# heart.net
KiCad netlist of a schematic drawn in EAGLE
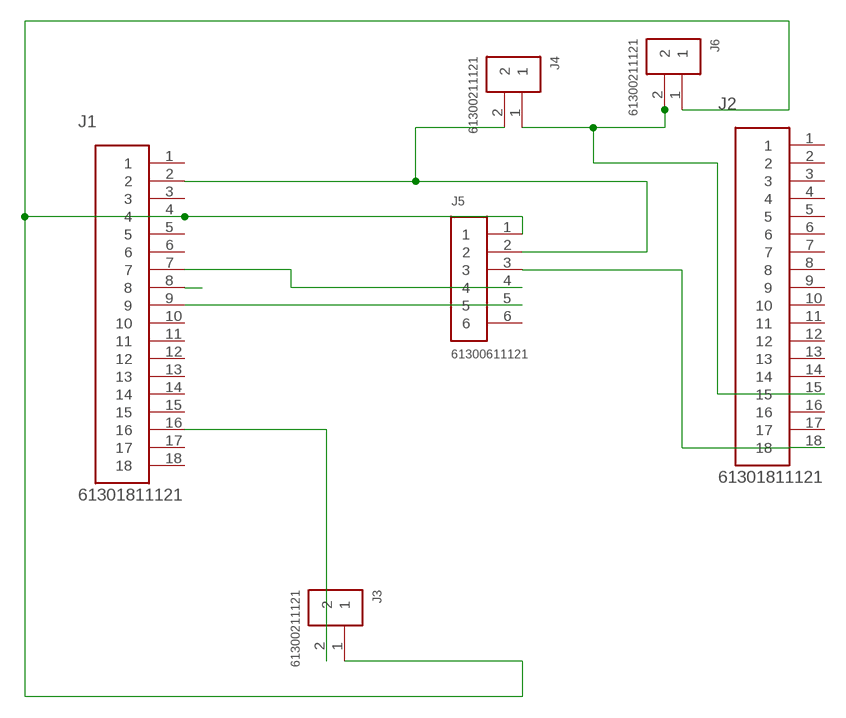
[diagram p0: schematic, sheet 1]

(export (version "E")
  (design (tool "Eeschema 10.0.6"))
  (components
    (comp (ref "J1")
      (value "61301811121")
      (footprint "eagle-import:61301811121")
      (fields
        (field (name "DIGIKEY_PART_NUMBER") "732-5328-ND")
        (field (name "MANUFACTURER") "Wurth Electronics Inc.")
        (field (name "CREATED_BY") "PCBLayout.com")
      )
      (libsource (lib "eagle-import") (part "61301811121"))
    )
    (comp (ref "J2")
      (value "61301811121")
      (footprint "eagle-import:61301811121")
      (fields
        (field (name "DIGIKEY_PART_NUMBER") "732-5328-ND")
        (field (name "MANUFACTURER") "Wurth Electronics Inc.")
        (field (name "CREATED_BY") "PCBLayout.com")
      )
      (libsource (lib "eagle-import") (part "61301811121"))
    )
    (comp (ref "J3")
      (value "61300211121")
      (footprint "eagle-import:61300211121")
      (fields
        (field (name "DIGI_KEY_PART_NUMBER") "732-5315-ND")
        (field (name "MANUFACTURER") "Wurth Electronics Inc.")
        (field (name "CREATED_BY") "PCBLayout.com")
      )
      (libsource (lib "eagle-import") (part "61300211121"))
    )
    (comp (ref "J4")
      (value "61300211121")
      (footprint "eagle-import:61300211121")
      (fields
        (field (name "DIGI_KEY_PART_NUMBER") "732-5315-ND")
        (field (name "MANUFACTURER") "Wurth Electronics Inc.")
        (field (name "CREATED_BY") "PCBLayout.com")
      )
      (libsource (lib "eagle-import") (part "61300211121"))
    )
    (comp (ref "J5")
      (value "61300611121")
      (footprint "eagle-import:61300611121")
      (fields
        (field (name "DIGI_KEY_PART_NUMBER") "732-5319-ND")
        (field (name "MANUFACTURER") "Wurth Electronics Inc.")
        (field (name "CREATED_BY") "PCBLayout.com")
      )
      (libsource (lib "eagle-import") (part "61300611121"))
    )
    (comp (ref "J6")
      (value "61300211121")
      (footprint "eagle-import:61300211121")
      (fields
        (field (name "DIGI_KEY_PART_NUMBER") "732-5315-ND")
        (field (name "MANUFACTURER") "Wurth Electronics Inc.")
        (field (name "CREATED_BY") "PCBLayout.com")
      )
      (libsource (lib "eagle-import") (part "61300211121"))
    )
  )
  (nets
    (net (code "1") (name "Net-(J1-Pad2)") (class "Default")
      (node (ref "J1") (pin "2") (pinfunction "2_2") (pintype "passive"))
      (node (ref "J4") (pin "2") (pinfunction "2_2") (pintype "passive"))
      (node (ref "J5") (pin "2") (pinfunction "2_2") (pintype "passive"))
    )
    (net (code "2") (name "Net-(J1-Pad4)") (class "Default")
      (node (ref "J1") (pin "4") (pinfunction "4_4") (pintype "passive"))
      (node (ref "J3") (pin "1") (pinfunction "1_1") (pintype "passive"))
      (node (ref "J5") (pin "1") (pinfunction "1_1") (pintype "passive"))
      (node (ref "J6") (pin "1") (pinfunction "1_1") (pintype "passive"))
    )
    (net (code "3") (name "Net-(J1-Pad7)") (class "Default")
      (node (ref "J1") (pin "7") (pinfunction "7_7") (pintype "passive"))
      (node (ref "J5") (pin "4") (pinfunction "4_4") (pintype "passive"))
    )
    (net (code "4") (name "Net-(J1-Pad9)") (class "Default")
      (node (ref "J1") (pin "9") (pinfunction "9_9") (pintype "passive"))
      (node (ref "J5") (pin "5") (pinfunction "5_5") (pintype "passive"))
    )
    (net (code "5") (name "Net-(J1-Pad16)") (class "Default")
      (node (ref "J1") (pin "16") (pinfunction "16_16") (pintype "passive"))
      (node (ref "J3") (pin "2") (pinfunction "2_2") (pintype "passive"))
    )
    (net (code "6") (name "Net-(J2-Pad15)") (class "Default")
      (node (ref "J2") (pin "15") (pinfunction "15_15") (pintype "passive"))
      (node (ref "J4") (pin "1") (pinfunction "1_1") (pintype "passive"))
      (node (ref "J6") (pin "2") (pinfunction "2_2") (pintype "passive"))
    )
    (net (code "7") (name "Net-(J2-Pad18)") (class "Default")
      (node (ref "J2") (pin "18") (pinfunction "18_18") (pintype "passive"))
      (node (ref "J5") (pin "3") (pinfunction "3_3") (pintype "passive"))
    )
    (net (code "8") (name "unconnected-(J1-Pad1)") (class "Default")
      (node (ref "J1") (pin "1") (pinfunction "1_1") (pintype "passive"))
    )
    (net (code "9") (name "unconnected-(J1-Pad3)") (class "Default")
      (node (ref "J1") (pin "3") (pinfunction "3_3") (pintype "passive"))
    )
    (net (code "10") (name "unconnected-(J1-Pad5)") (class "Default")
      (node (ref "J1") (pin "5") (pinfunction "5_5") (pintype "passive"))
    )
    (net (code "11") (name "unconnected-(J1-Pad6)") (class "Default")
      (node (ref "J1") (pin "6") (pinfunction "6_6") (pintype "passive"))
    )
    (net (code "12") (name "unconnected-(J1-Pad8)") (class "Default")
      (node (ref "J1") (pin "8") (pinfunction "8_8") (pintype "passive"))
    )
    (net (code "13") (name "unconnected-(J1-Pad10)") (class "Default")
      (node (ref "J1") (pin "10") (pinfunction "10_10") (pintype "passive"))
    )
    (net (code "14") (name "unconnected-(J1-Pad11)") (class "Default")
      (node (ref "J1") (pin "11") (pinfunction "11_11") (pintype "passive"))
    )
    (net (code "15") (name "unconnected-(J1-Pad12)") (class "Default")
      (node (ref "J1") (pin "12") (pinfunction "12_12") (pintype "passive"))
    )
    (net (code "16") (name "unconnected-(J1-Pad13)") (class "Default")
      (node (ref "J1") (pin "13") (pinfunction "13_13") (pintype "passive"))
    )
    (net (code "17") (name "unconnected-(J1-Pad14)") (class "Default")
      (node (ref "J1") (pin "14") (pinfunction "14_14") (pintype "passive"))
    )
    (net (code "18") (name "unconnected-(J1-Pad15)") (class "Default")
      (node (ref "J1") (pin "15") (pinfunction "15_15") (pintype "passive"))
    )
    (net (code "19") (name "unconnected-(J1-Pad17)") (class "Default")
      (node (ref "J1") (pin "17") (pinfunction "17_17") (pintype "passive"))
    )
    (net (code "20") (name "unconnected-(J1-Pad18)") (class "Default")
      (node (ref "J1") (pin "18") (pinfunction "18_18") (pintype "passive"))
    )
    (net (code "21") (name "unconnected-(J2-Pad1)") (class "Default")
      (node (ref "J2") (pin "1") (pinfunction "1_1") (pintype "passive"))
    )
    (net (code "22") (name "unconnected-(J2-Pad2)") (class "Default")
      (node (ref "J2") (pin "2") (pinfunction "2_2") (pintype "passive"))
    )
    (net (code "23") (name "unconnected-(J2-Pad3)") (class "Default")
      (node (ref "J2") (pin "3") (pinfunction "3_3") (pintype "passive"))
    )
    (net (code "24") (name "unconnected-(J2-Pad4)") (class "Default")
      (node (ref "J2") (pin "4") (pinfunction "4_4") (pintype "passive"))
    )
    (net (code "25") (name "unconnected-(J2-Pad5)") (class "Default")
      (node (ref "J2") (pin "5") (pinfunction "5_5") (pintype "passive"))
    )
    (net (code "26") (name "unconnected-(J2-Pad6)") (class "Default")
      (node (ref "J2") (pin "6") (pinfunction "6_6") (pintype "passive"))
    )
    (net (code "27") (name "unconnected-(J2-Pad7)") (class "Default")
      (node (ref "J2") (pin "7") (pinfunction "7_7") (pintype "passive"))
    )
    (net (code "28") (name "unconnected-(J2-Pad8)") (class "Default")
      (node (ref "J2") (pin "8") (pinfunction "8_8") (pintype "passive"))
    )
    (net (code "29") (name "unconnected-(J2-Pad9)") (class "Default")
      (node (ref "J2") (pin "9") (pinfunction "9_9") (pintype "passive"))
    )
    (net (code "30") (name "unconnected-(J2-Pad10)") (class "Default")
      (node (ref "J2") (pin "10") (pinfunction "10_10") (pintype "passive"))
    )
    (net (code "31") (name "unconnected-(J2-Pad11)") (class "Default")
      (node (ref "J2") (pin "11") (pinfunction "11_11") (pintype "passive"))
    )
    (net (code "32") (name "unconnected-(J2-Pad12)") (class "Default")
      (node (ref "J2") (pin "12") (pinfunction "12_12") (pintype "passive"))
    )
    (net (code "33") (name "unconnected-(J2-Pad13)") (class "Default")
      (node (ref "J2") (pin "13") (pinfunction "13_13") (pintype "passive"))
    )
    (net (code "34") (name "unconnected-(J2-Pad14)") (class "Default")
      (node (ref "J2") (pin "14") (pinfunction "14_14") (pintype "passive"))
    )
    (net (code "35") (name "unconnected-(J2-Pad16)") (class "Default")
      (node (ref "J2") (pin "16") (pinfunction "16_16") (pintype "passive"))
    )
    (net (code "36") (name "unconnected-(J2-Pad17)") (class "Default")
      (node (ref "J2") (pin "17") (pinfunction "17_17") (pintype "passive"))
    )
    (net (code "37") (name "unconnected-(J5-Pad6)") (class "Default")
      (node (ref "J5") (pin "6") (pinfunction "6_6") (pintype "passive"))
    )
  )
)
